# Project-PowerSwitch-Final.net
KiCad netlist of a schematic drawn in EAGLE
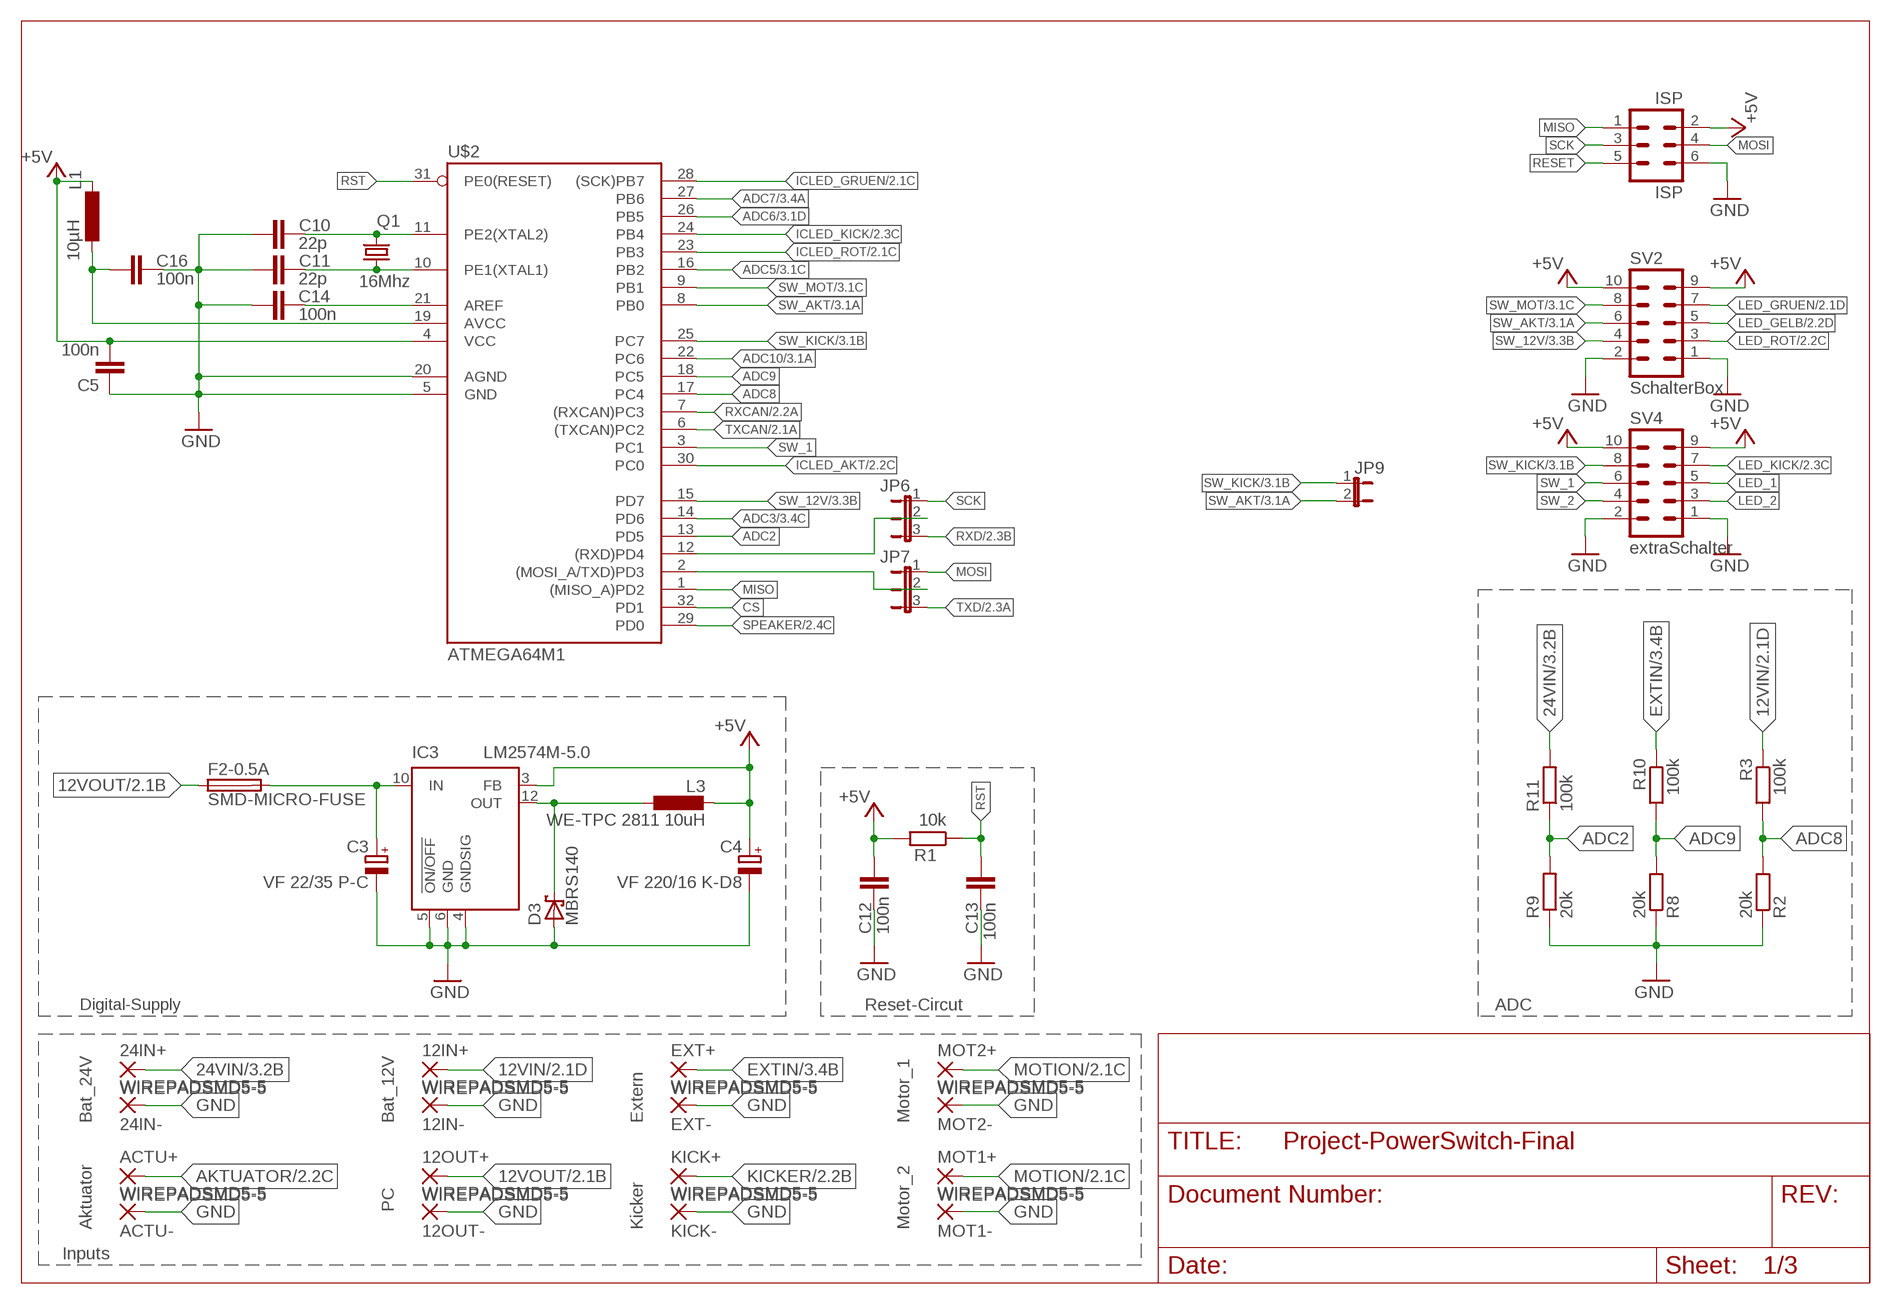
[diagram p0: schematic, sheet 1]
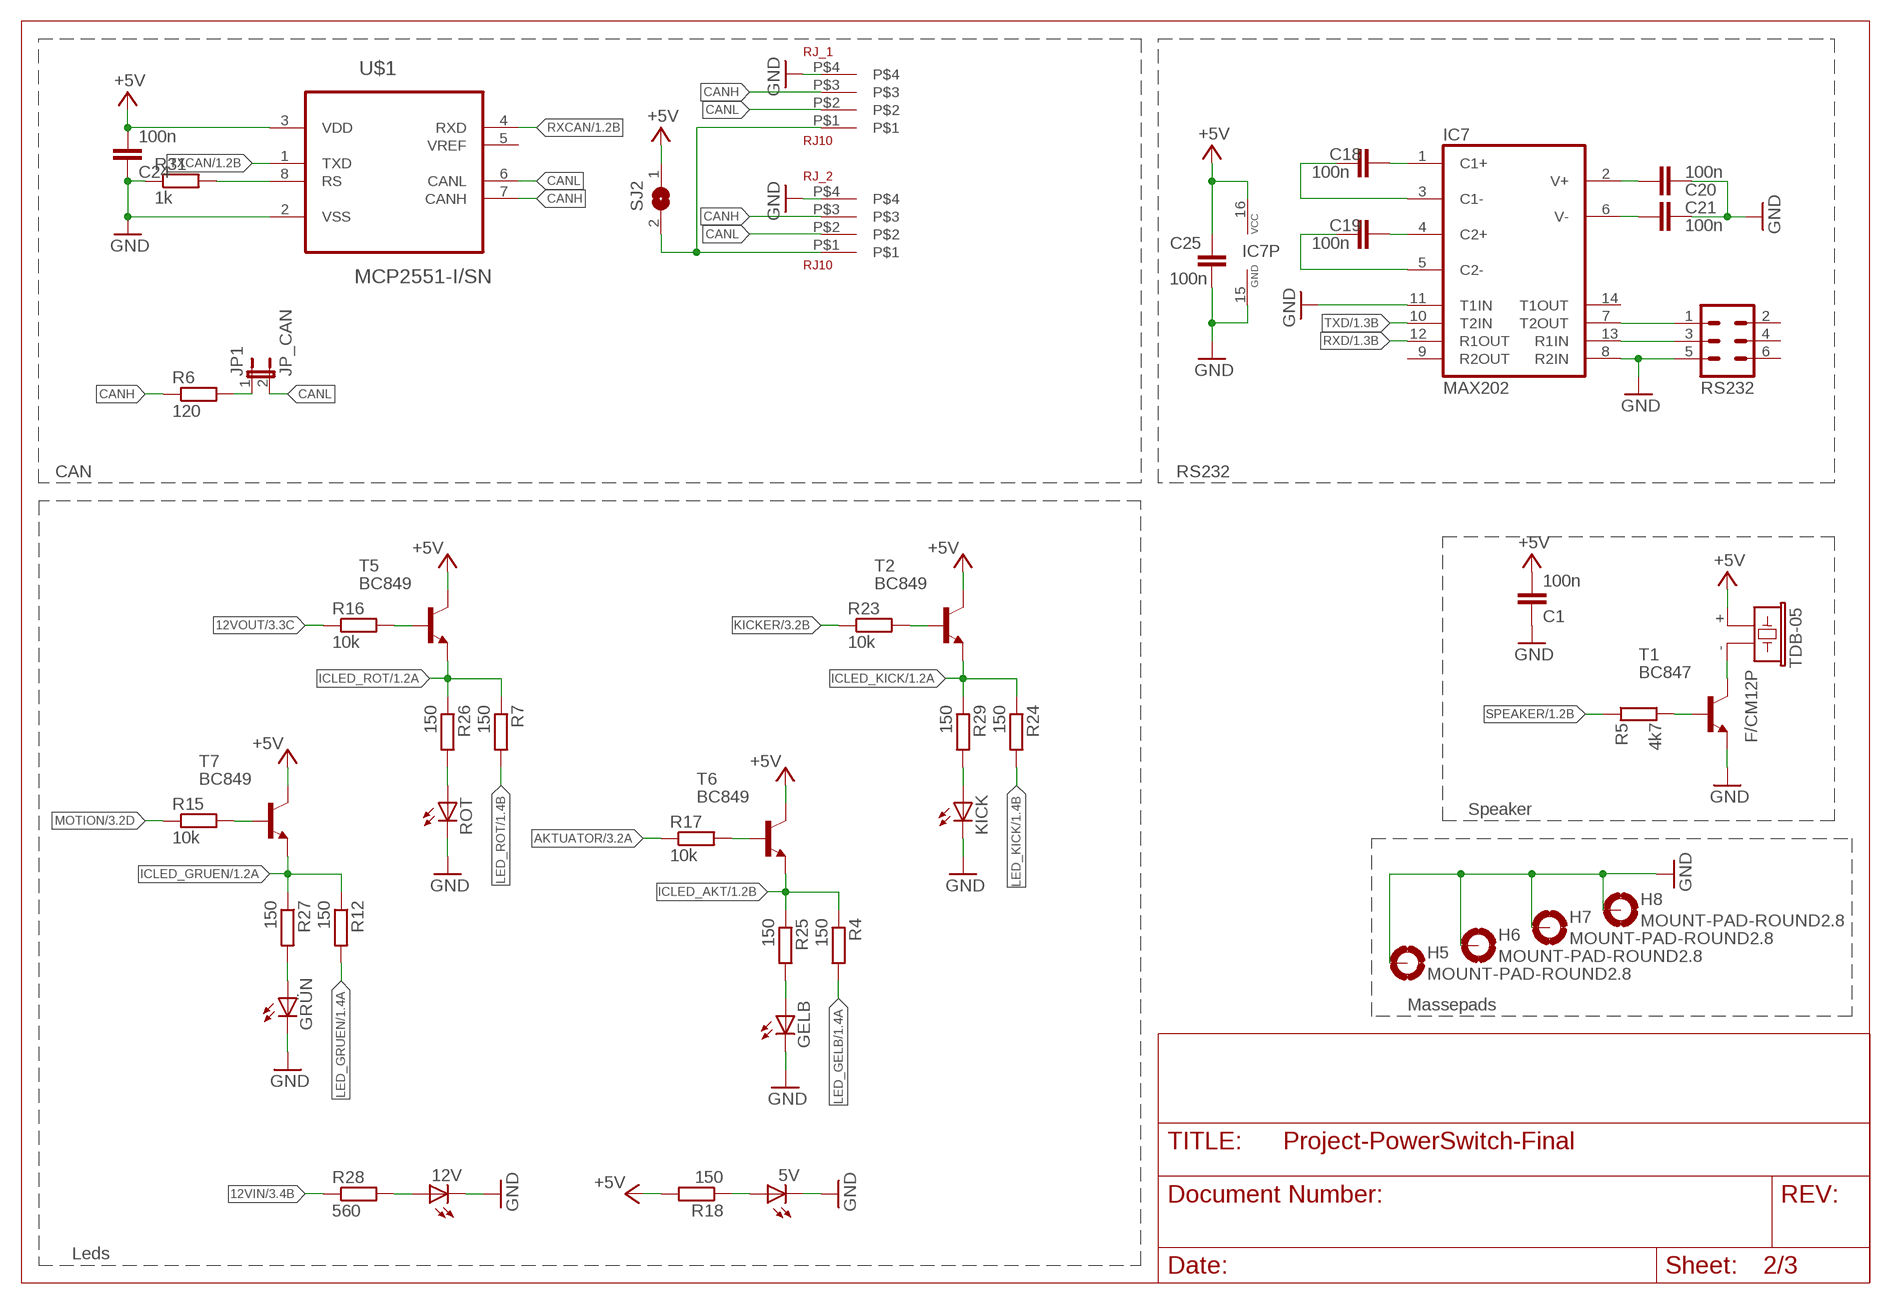
[diagram p1: schematic, sheet 2]
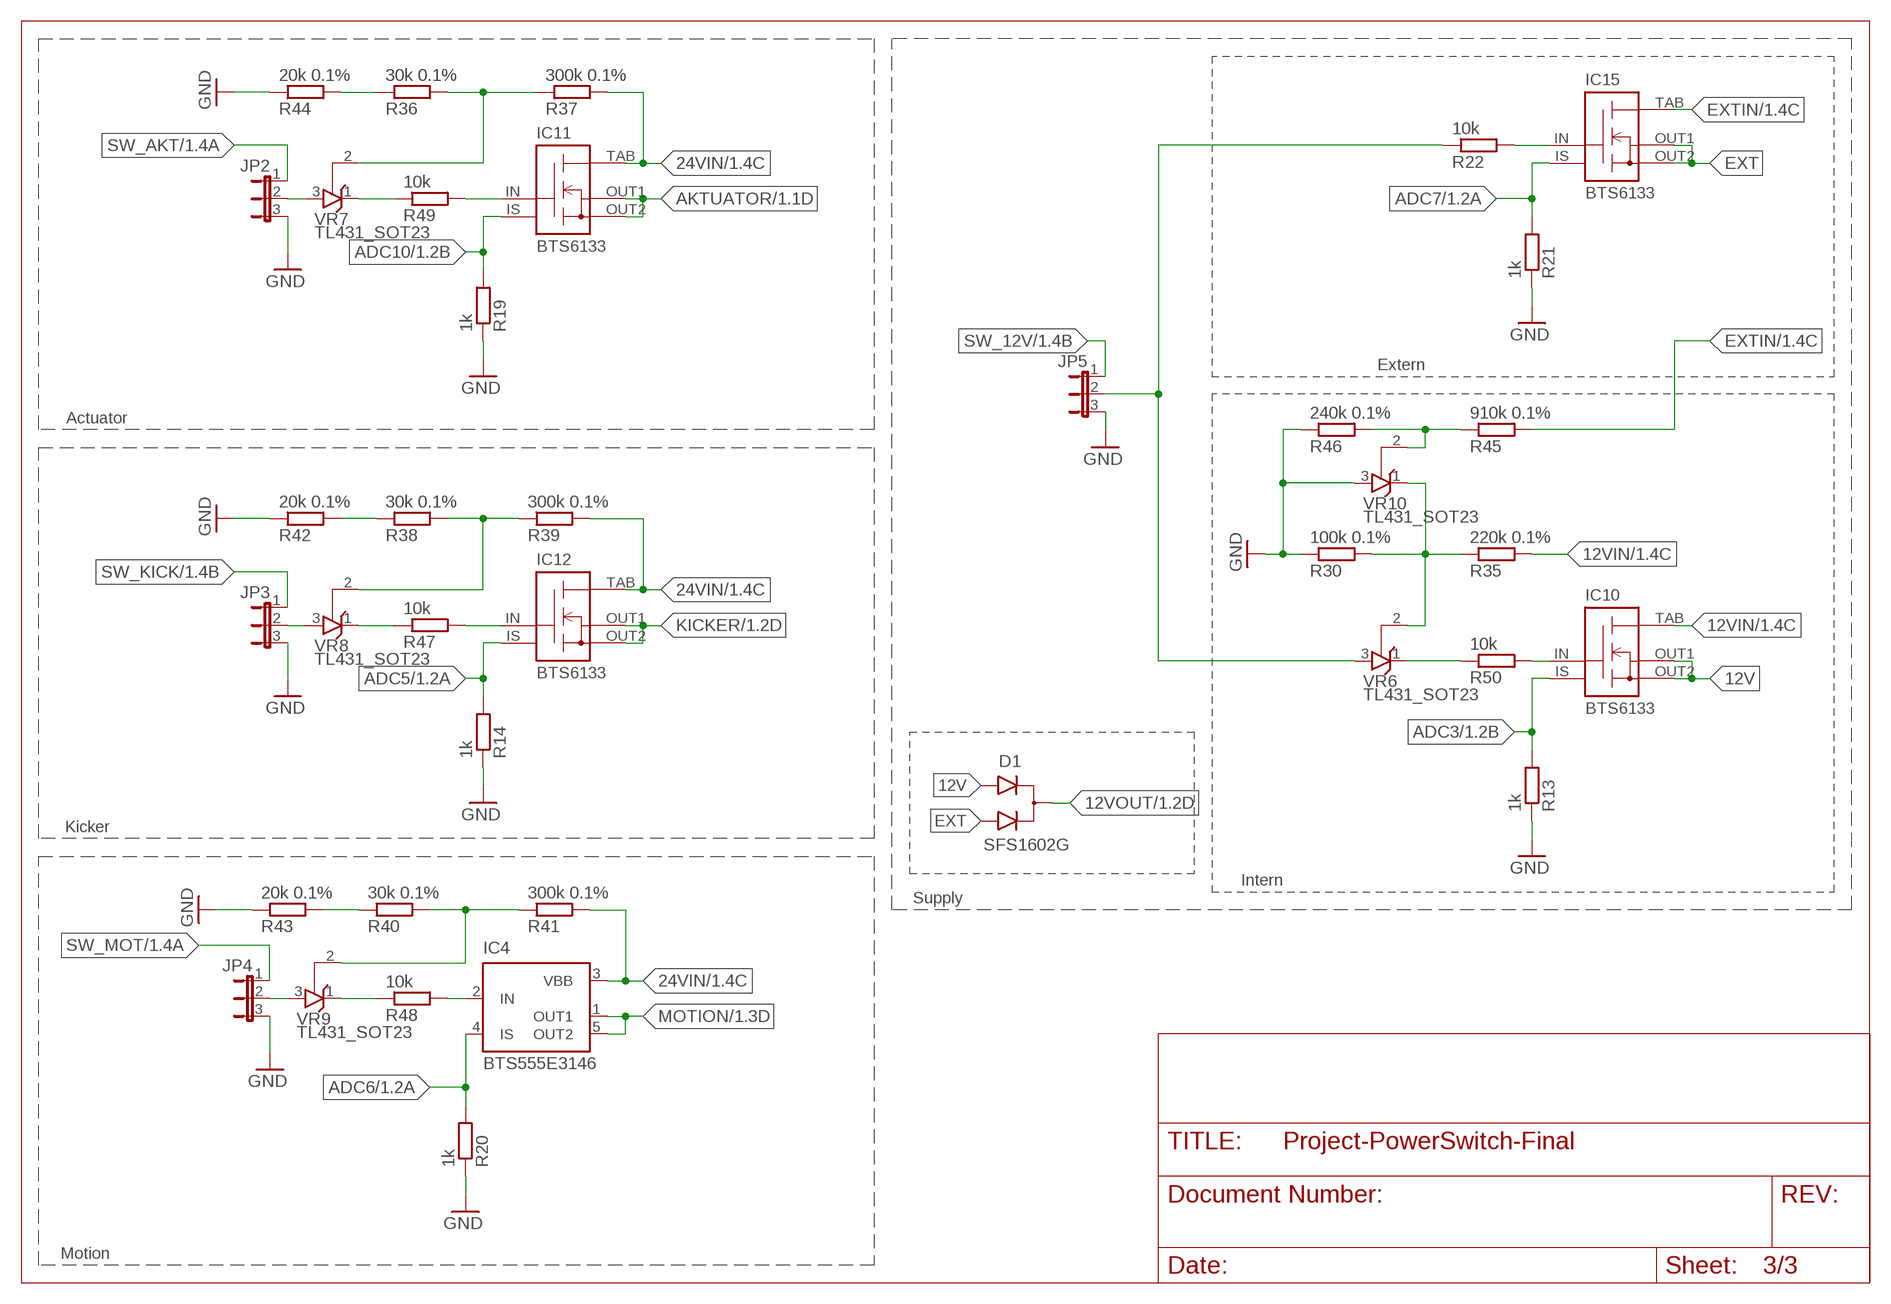
[diagram p2: schematic, sheet 3]

(export (version "E")
  (design (tool "Eeschema 10.0.6"))
  (components
    (comp (ref "D1")
      (value "SFS1602G")
      (footprint "eagle-import:D2PAK")
      (libsource (lib "eagle-import") (part "SFS160G"))
    )
    (comp (ref "IC4")
      (value "BTS555E3146")
      (footprint "eagle-import:TO220-52")
      (libsource (lib "eagle-import") (part "BTS555E3146"))
    )
    (comp (ref "IC10")
      (value "BTS6133")
      (footprint "eagle-import:TO252-51")
      (libsource (lib "eagle-import") (part "BTS6133"))
    )
    (comp (ref "IC11")
      (value "BTS6133")
      (footprint "eagle-import:TO252-51")
      (libsource (lib "eagle-import") (part "BTS6133"))
    )
    (comp (ref "IC12")
      (value "BTS6133")
      (footprint "eagle-import:TO252-51")
      (libsource (lib "eagle-import") (part "BTS6133"))
    )
    (comp (ref "IC15")
      (value "BTS6133")
      (footprint "eagle-import:TO252-51")
      (libsource (lib "eagle-import") (part "BTS6133"))
    )
    (comp (ref "JP2")
      (value "JP2E")
      (footprint "eagle-import:JP2")
      (libsource (lib "eagle-import") (part "JP2E"))
    )
    (comp (ref "JP3")
      (value "JP2E")
      (footprint "eagle-import:JP2")
      (libsource (lib "eagle-import") (part "JP2E"))
    )
    (comp (ref "JP4")
      (value "JP2E")
      (footprint "eagle-import:JP2")
      (libsource (lib "eagle-import") (part "JP2E"))
    )
    (comp (ref "JP5")
      (value "JP2E")
      (footprint "eagle-import:JP2")
      (libsource (lib "eagle-import") (part "JP2E"))
    )
    (comp (ref "R13")
      (value "1k")
      (footprint "eagle-import:R0805")
      (libsource (lib "eagle-import") (part "R-EU_R0805"))
    )
    (comp (ref "R14")
      (value "1k")
      (footprint "eagle-import:R0805")
      (libsource (lib "eagle-import") (part "R-EU_R0805"))
    )
    (comp (ref "R19")
      (value "1k")
      (footprint "eagle-import:R0805")
      (libsource (lib "eagle-import") (part "R-EU_R0805"))
    )
    (comp (ref "R20")
      (value "1k")
      (footprint "eagle-import:R0805")
      (libsource (lib "eagle-import") (part "R-EU_R0805"))
    )
    (comp (ref "R21")
      (value "1k")
      (footprint "eagle-import:R0805")
      (libsource (lib "eagle-import") (part "R-EU_R0805"))
    )
    (comp (ref "R22")
      (value "10k")
      (footprint "eagle-import:R0805")
      (libsource (lib "eagle-import") (part "R-EU_R0805"))
    )
    (comp (ref "R30")
      (value "100k 0.1%")
      (footprint "eagle-import:R0805")
      (libsource (lib "eagle-import") (part "R-EU_R0805"))
    )
    (comp (ref "R35")
      (value "220k 0.1%")
      (footprint "eagle-import:R0805")
      (libsource (lib "eagle-import") (part "R-EU_R0805"))
    )
    (comp (ref "R36")
      (value "30k 0.1%")
      (footprint "eagle-import:R0805")
      (libsource (lib "eagle-import") (part "R-EU_R0805"))
    )
    (comp (ref "R37")
      (value "300k 0.1%")
      (footprint "eagle-import:R0805")
      (libsource (lib "eagle-import") (part "R-EU_R0805"))
    )
    (comp (ref "R38")
      (value "30k 0.1%")
      (footprint "eagle-import:R0805")
      (libsource (lib "eagle-import") (part "R-EU_R0805"))
    )
    (comp (ref "R39")
      (value "300k 0.1%")
      (footprint "eagle-import:R0805")
      (libsource (lib "eagle-import") (part "R-EU_R0805"))
    )
    (comp (ref "R40")
      (value "30k 0.1%")
      (footprint "eagle-import:R0805")
      (libsource (lib "eagle-import") (part "R-EU_R0805"))
    )
    (comp (ref "R41")
      (value "300k 0.1%")
      (footprint "eagle-import:R0805")
      (libsource (lib "eagle-import") (part "R-EU_R0805"))
    )
    (comp (ref "R42")
      (value "20k 0.1%")
      (footprint "eagle-import:R0805")
      (libsource (lib "eagle-import") (part "R-EU_R0805"))
    )
    (comp (ref "R43")
      (value "20k 0.1%")
      (footprint "eagle-import:R0805")
      (libsource (lib "eagle-import") (part "R-EU_R0805"))
    )
    (comp (ref "R44")
      (value "20k 0.1%")
      (footprint "eagle-import:R0805")
      (libsource (lib "eagle-import") (part "R-EU_R0805"))
    )
    (comp (ref "R45")
      (value "910k 0.1%")
      (footprint "eagle-import:R0805")
      (libsource (lib "eagle-import") (part "R-EU_R0805"))
    )
    (comp (ref "R46")
      (value "240k 0.1%")
      (footprint "eagle-import:R0805")
      (libsource (lib "eagle-import") (part "R-EU_R0805"))
    )
    (comp (ref "R47")
      (value "10k")
      (footprint "eagle-import:R0805")
      (libsource (lib "eagle-import") (part "R-EU_R0805"))
    )
    (comp (ref "R48")
      (value "10k")
      (footprint "eagle-import:R0805")
      (libsource (lib "eagle-import") (part "R-EU_R0805"))
    )
    (comp (ref "R49")
      (value "10k")
      (footprint "eagle-import:R0805")
      (libsource (lib "eagle-import") (part "R-EU_R0805"))
    )
    (comp (ref "R50")
      (value "10k")
      (footprint "eagle-import:R0805")
      (libsource (lib "eagle-import") (part "R-EU_R0805"))
    )
    (comp (ref "VR6")
      (value "TL431_SOT23")
      (footprint "eagle-import:SOT23")
      (libsource (lib "eagle-import") (part "TL431_SOT23"))
    )
    (comp (ref "VR7")
      (value "TL431_SOT23")
      (footprint "eagle-import:SOT23")
      (libsource (lib "eagle-import") (part "TL431_SOT23"))
    )
    (comp (ref "VR8")
      (value "TL431_SOT23")
      (footprint "eagle-import:SOT23")
      (libsource (lib "eagle-import") (part "TL431_SOT23"))
    )
    (comp (ref "VR9")
      (value "TL431_SOT23")
      (footprint "eagle-import:SOT23")
      (libsource (lib "eagle-import") (part "TL431_SOT23"))
    )
    (comp (ref "VR10")
      (value "TL431_SOT23")
      (footprint "eagle-import:SOT23")
      (libsource (lib "eagle-import") (part "TL431_SOT23"))
    )
    (comp (ref "5V")
      (value "LEDCHIPLED_0805")
      (footprint "eagle-import:CHIPLED_0805")
      (libsource (lib "eagle-import") (part "LEDCHIPLED_0805"))
    )
    (comp (ref "12V")
      (value "LEDCHIPLED_0805")
      (footprint "eagle-import:CHIPLED_0805")
      (libsource (lib "eagle-import") (part "LEDCHIPLED_0805"))
    )
    (comp (ref "C1")
      (value "100n")
      (footprint "eagle-import:C0603")
      (libsource (lib "eagle-import") (part "C-EUC0603"))
    )
    (comp (ref "C18")
      (value "100n")
      (footprint "eagle-import:C0603K")
      (libsource (lib "eagle-import") (part "C-EUC0603K"))
    )
    (comp (ref "C19")
      (value "100n")
      (footprint "eagle-import:C0603K")
      (libsource (lib "eagle-import") (part "C-EUC0603K"))
    )
    (comp (ref "C20")
      (value "100n")
      (footprint "eagle-import:C0603K")
      (libsource (lib "eagle-import") (part "C-EUC0603K"))
    )
    (comp (ref "C21")
      (value "100n")
      (footprint "eagle-import:C0603K")
      (libsource (lib "eagle-import") (part "C-EUC0603K"))
    )
    (comp (ref "C24")
      (value "100n")
      (footprint "eagle-import:C0603")
      (libsource (lib "eagle-import") (part "C-EUC0603"))
    )
    (comp (ref "C25")
      (value "100n")
      (footprint "eagle-import:C0603K")
      (libsource (lib "eagle-import") (part "C-EUC0603K"))
    )
    (comp (ref "GELB")
      (value "LEDCHIPLED_0805")
      (footprint "eagle-import:CHIPLED_0805")
      (libsource (lib "eagle-import") (part "LEDCHIPLED_0805"))
    )
    (comp (ref "GRÜN")
      (value "LEDCHIPLED_0805")
      (footprint "eagle-import:CHIPLED_0805")
      (libsource (lib "eagle-import") (part "LEDCHIPLED_0805"))
    )
    (comp (ref "H5")
      (value "MOUNT-PAD-ROUND2.8")
      (footprint "eagle-import:2,8-PAD")
      (libsource (lib "eagle-import") (part "MOUNT-PAD-ROUND2.8"))
    )
    (comp (ref "H6")
      (value "MOUNT-PAD-ROUND2.8")
      (footprint "eagle-import:2,8-PAD")
      (libsource (lib "eagle-import") (part "MOUNT-PAD-ROUND2.8"))
    )
    (comp (ref "H7")
      (value "MOUNT-PAD-ROUND2.8")
      (footprint "eagle-import:2,8-PAD")
      (libsource (lib "eagle-import") (part "MOUNT-PAD-ROUND2.8"))
    )
    (comp (ref "H8")
      (value "MOUNT-PAD-ROUND2.8")
      (footprint "eagle-import:2,8-PAD")
      (libsource (lib "eagle-import") (part "MOUNT-PAD-ROUND2.8"))
    )
    (comp (ref "IC7")
      (value "MAX202")
      (footprint "eagle-import:SO16")
      (fields (field (name "MPN") "MAX3232CSE"))
      (libsource (lib "eagle-import") (part "MAX3232SEC"))
    )
    (comp (ref "JP1")
      (value "JP_CAN")
      (footprint "eagle-import:JP1")
      (libsource (lib "eagle-import") (part "JP1E"))
    )
    (comp (ref "KICK")
      (value "LEDCHIPLED_0805")
      (footprint "eagle-import:CHIPLED_0805")
      (libsource (lib "eagle-import") (part "LEDCHIPLED_0805"))
    )
    (comp (ref "R4")
      (value "150")
      (footprint "eagle-import:R0805")
      (libsource (lib "eagle-import") (part "R-EU_R0805"))
    )
    (comp (ref "R5")
      (value "4k7")
      (footprint "eagle-import:R0805")
      (libsource (lib "eagle-import") (part "R-EU_R0805"))
    )
    (comp (ref "R6")
      (value "120")
      (footprint "eagle-import:M0805")
      (libsource (lib "eagle-import") (part "R-EU_M0805"))
    )
    (comp (ref "R7")
      (value "150")
      (footprint "eagle-import:R0805")
      (libsource (lib "eagle-import") (part "R-EU_R0805"))
    )
    (comp (ref "R12")
      (value "150")
      (footprint "eagle-import:R0805")
      (libsource (lib "eagle-import") (part "R-EU_R0805"))
    )
    (comp (ref "R15")
      (value "10k")
      (footprint "eagle-import:R0805")
      (libsource (lib "eagle-import") (part "R-EU_R0805"))
    )
    (comp (ref "R16")
      (value "10k")
      (footprint "eagle-import:R0805")
      (libsource (lib "eagle-import") (part "R-EU_R0805"))
    )
    (comp (ref "R17")
      (value "10k")
      (footprint "eagle-import:R0805")
      (libsource (lib "eagle-import") (part "R-EU_R0805"))
    )
    (comp (ref "R18")
      (value "150")
      (footprint "eagle-import:R0805")
      (libsource (lib "eagle-import") (part "R-EU_R0805"))
    )
    (comp (ref "R23")
      (value "10k")
      (footprint "eagle-import:R0805")
      (libsource (lib "eagle-import") (part "R-EU_R0805"))
    )
    (comp (ref "R24")
      (value "150")
      (footprint "eagle-import:R0805")
      (libsource (lib "eagle-import") (part "R-EU_R0805"))
    )
    (comp (ref "R25")
      (value "150")
      (footprint "eagle-import:R0805")
      (libsource (lib "eagle-import") (part "R-EU_R0805"))
    )
    (comp (ref "R26")
      (value "150")
      (footprint "eagle-import:R0805")
      (libsource (lib "eagle-import") (part "R-EU_R0805"))
    )
    (comp (ref "R27")
      (value "150")
      (footprint "eagle-import:R0805")
      (libsource (lib "eagle-import") (part "R-EU_R0805"))
    )
    (comp (ref "R28")
      (value "560")
      (footprint "eagle-import:R0805")
      (libsource (lib "eagle-import") (part "R-EU_R0805"))
    )
    (comp (ref "R29")
      (value "150")
      (footprint "eagle-import:R0805")
      (libsource (lib "eagle-import") (part "R-EU_R0805"))
    )
    (comp (ref "R31")
      (value "1k")
      (footprint "eagle-import:R0805")
      (libsource (lib "eagle-import") (part "R-EU_R0805"))
    )
    (comp (ref "RJ_1")
      (value "RJ10")
      (footprint "eagle-import:RJ10")
      (libsource (lib "eagle-import") (part "RJ10"))
    )
    (comp (ref "RJ_2")
      (value "RJ10")
      (footprint "eagle-import:RJ10")
      (libsource (lib "eagle-import") (part "RJ10"))
    )
    (comp (ref "ROT")
      (value "LEDCHIPLED_0805")
      (footprint "eagle-import:CHIPLED_0805")
      (libsource (lib "eagle-import") (part "LEDCHIPLED_0805"))
    )
    (comp (ref "RS232")
      (value "ML6")
      (footprint "eagle-import:ML6")
      (libsource (lib "eagle-import") (part "ML6"))
    )
    (comp (ref "SJ2") (value "SJ") (footprint "eagle-import:SJ") (libsource (lib "eagle-import") (part "SJ")))
    (comp (ref "T1")
      (value "BC847")
      (footprint "eagle-import:SOT23")
      (libsource (lib "eagle-import") (part "BC847"))
    )
    (comp (ref "T2")
      (value "BC849")
      (footprint "eagle-import:SOT23")
      (libsource (lib "eagle-import") (part "BC849"))
    )
    (comp (ref "T5")
      (value "BC849")
      (footprint "eagle-import:SOT23")
      (libsource (lib "eagle-import") (part "BC849"))
    )
    (comp (ref "T6")
      (value "BC849")
      (footprint "eagle-import:SOT23")
      (libsource (lib "eagle-import") (part "BC849"))
    )
    (comp (ref "T7")
      (value "BC849")
      (footprint "eagle-import:SOT23")
      (libsource (lib "eagle-import") (part "BC849"))
    )
    (comp (ref "TDB-05")
      (value "F/CM12P")
      (footprint "eagle-import:F_CM12P")
      (libsource (lib "eagle-import") (part "F/CM12P"))
    )
    (comp (ref "U$1")
      (value "MCP2551-I/SN")
      (footprint "eagle-import:SOIC127P600X175-8N")
      (libsource (lib "eagle-import") (part "MCP2551-I/SN"))
    )
    (comp (ref "12IN+")
      (value "WIREPADSMD5-5")
      (footprint "eagle-import:5-5")
      (libsource (lib "eagle-import") (part "WIREPADSMD5-5"))
    )
    (comp (ref "12IN-")
      (value "WIREPADSMD5-5")
      (footprint "eagle-import:5-5")
      (libsource (lib "eagle-import") (part "WIREPADSMD5-5"))
    )
    (comp (ref "12OUT+")
      (value "WIREPADSMD5-5")
      (footprint "eagle-import:5-5")
      (libsource (lib "eagle-import") (part "WIREPADSMD5-5"))
    )
    (comp (ref "12OUT-")
      (value "WIREPADSMD5-5")
      (footprint "eagle-import:5-5")
      (libsource (lib "eagle-import") (part "WIREPADSMD5-5"))
    )
    (comp (ref "24IN+")
      (value "WIREPADSMD5-5")
      (footprint "eagle-import:5-5")
      (libsource (lib "eagle-import") (part "WIREPADSMD5-5"))
    )
    (comp (ref "24IN-")
      (value "WIREPADSMD5-5")
      (footprint "eagle-import:5-5")
      (libsource (lib "eagle-import") (part "WIREPADSMD5-5"))
    )
    (comp (ref "ACTU+")
      (value "WIREPADSMD5-5")
      (footprint "eagle-import:5-5")
      (libsource (lib "eagle-import") (part "WIREPADSMD5-5"))
    )
    (comp (ref "ACTU-")
      (value "WIREPADSMD5-5")
      (footprint "eagle-import:5-5")
      (libsource (lib "eagle-import") (part "WIREPADSMD5-5"))
    )
    (comp (ref "C3")
      (value "VF 22/35 P-C")
      (footprint "eagle-import:PANASONIC_C")
      (libsource (lib "eagle-import") (part "CPOL-EUC"))
    )
    (comp (ref "C4")
      (value "VF 220/16 K-D8")
      (footprint "eagle-import:PANASONIC_D")
      (libsource (lib "eagle-import") (part "CPOL-EUD"))
    )
    (comp (ref "C5")
      (value "100n")
      (footprint "eagle-import:C0603K")
      (libsource (lib "eagle-import") (part "C-EUC0603K"))
    )
    (comp (ref "C10")
      (value "22p")
      (footprint "eagle-import:C0603K")
      (libsource (lib "eagle-import") (part "C-EUC0603K"))
    )
    (comp (ref "C11")
      (value "22p")
      (footprint "eagle-import:C0603K")
      (libsource (lib "eagle-import") (part "C-EUC0603K"))
    )
    (comp (ref "C12")
      (value "100n")
      (footprint "eagle-import:C0603K")
      (libsource (lib "eagle-import") (part "C-EUC0603K"))
    )
    (comp (ref "C13")
      (value "100n")
      (footprint "eagle-import:C0603K")
      (libsource (lib "eagle-import") (part "C-EUC0603K"))
    )
    (comp (ref "C14")
      (value "100n")
      (footprint "eagle-import:C0603K")
      (libsource (lib "eagle-import") (part "C-EUC0603K"))
    )
    (comp (ref "C16")
      (value "100n")
      (footprint "eagle-import:C0603K")
      (libsource (lib "eagle-import") (part "C-EUC0603K"))
    )
    (comp (ref "D3")
      (value "MBRS140")
      (footprint "eagle-import:SMB")
      (libsource (lib "eagle-import") (part "SCHOTTKY-DIODESMD"))
    )
    (comp (ref "EXT+")
      (value "WIREPADSMD5-5")
      (footprint "eagle-import:5-5")
      (libsource (lib "eagle-import") (part "WIREPADSMD5-5"))
    )
    (comp (ref "EXT-")
      (value "WIREPADSMD5-5")
      (footprint "eagle-import:5-5")
      (libsource (lib "eagle-import") (part "WIREPADSMD5-5"))
    )
    (comp (ref "F2-0.5A")
      (value "SMD-MICRO-FUSE")
      (footprint "eagle-import:SMD-6,1X2,6")
      (libsource (lib "eagle-import") (part "SMD-MICRO-FUSE"))
    )
    (comp (ref "IC3")
      (value "LM2574M-5.0")
      (footprint "eagle-import:SO14W")
      (libsource (lib "eagle-import") (part "LM2574?-M5.0"))
    )
    (comp (ref "ISP")
      (value "ISP")
      (footprint "eagle-import:ML6")
      (libsource (lib "eagle-import") (part "ML6"))
    )
    (comp (ref "JP6")
      (value "JP2E")
      (footprint "eagle-import:JP2")
      (libsource (lib "eagle-import") (part "JP2E"))
    )
    (comp (ref "JP7")
      (value "JP2E")
      (footprint "eagle-import:JP2")
      (libsource (lib "eagle-import") (part "JP2E"))
    )
    (comp (ref "JP9")
      (value "JP1E")
      (footprint "eagle-import:JP1")
      (libsource (lib "eagle-import") (part "JP1E"))
    )
    (comp (ref "KICK+")
      (value "WIREPADSMD5-5")
      (footprint "eagle-import:5-5")
      (libsource (lib "eagle-import") (part "WIREPADSMD5-5"))
    )
    (comp (ref "KICK-")
      (value "WIREPADSMD5-5")
      (footprint "eagle-import:5-5")
      (libsource (lib "eagle-import") (part "WIREPADSMD5-5"))
    )
    (comp (ref "L1")
      (value "10µH")
      (footprint "eagle-import:R0805")
      (libsource (lib "eagle-import") (part "L-EU-0805L0805"))
    )
    (comp (ref "L3")
      (value "WE-TPC 2811 10uH")
      (footprint "eagle-import:POWER-CHOKE_WE-TPC")
      (libsource (lib "eagle-import") (part "L-EUWE-TPC"))
    )
    (comp (ref "MOT1+")
      (value "WIREPADSMD5-5")
      (footprint "eagle-import:5-5")
      (libsource (lib "eagle-import") (part "WIREPADSMD5-5"))
    )
    (comp (ref "MOT1-")
      (value "WIREPADSMD5-5")
      (footprint "eagle-import:5-5")
      (libsource (lib "eagle-import") (part "WIREPADSMD5-5"))
    )
    (comp (ref "MOT2+")
      (value "WIREPADSMD5-5")
      (footprint "eagle-import:5-5")
      (libsource (lib "eagle-import") (part "WIREPADSMD5-5"))
    )
    (comp (ref "MOT2-")
      (value "WIREPADSMD5-5")
      (footprint "eagle-import:5-5")
      (libsource (lib "eagle-import") (part "WIREPADSMD5-5"))
    )
    (comp (ref "Q1")
      (value "16Mhz")
      (footprint "eagle-import:HC49U-V@1")
      (libsource (lib "eagle-import") (part "CRYTALHC49U-V"))
    )
    (comp (ref "R1")
      (value "10k")
      (footprint "eagle-import:R0805")
      (libsource (lib "eagle-import") (part "R-EU_R0805"))
    )
    (comp (ref "R2")
      (value "20k")
      (footprint "eagle-import:R0805")
      (libsource (lib "eagle-import") (part "R-EU_R0805"))
    )
    (comp (ref "R3")
      (value "100k")
      (footprint "eagle-import:R0805")
      (libsource (lib "eagle-import") (part "R-EU_R0805"))
    )
    (comp (ref "R8")
      (value "20k")
      (footprint "eagle-import:R0805")
      (libsource (lib "eagle-import") (part "R-EU_R0805"))
    )
    (comp (ref "R9")
      (value "20k")
      (footprint "eagle-import:R0805")
      (libsource (lib "eagle-import") (part "R-EU_R0805"))
    )
    (comp (ref "R10")
      (value "100k")
      (footprint "eagle-import:R0805")
      (libsource (lib "eagle-import") (part "R-EU_R0805"))
    )
    (comp (ref "R11")
      (value "100k")
      (footprint "eagle-import:R0805")
      (libsource (lib "eagle-import") (part "R-EU_R0805"))
    )
    (comp (ref "SV2")
      (value "SchalterBox")
      (footprint "eagle-import:ML10")
      (libsource (lib "eagle-import") (part "ML10"))
    )
    (comp (ref "SV4")
      (value "extraSchalter")
      (footprint "eagle-import:ML10")
      (libsource (lib "eagle-import") (part "ML10"))
    )
    (comp (ref "U$2")
      (value "ATMEGA64M1")
      (footprint "eagle-import:TQFP32-08")
      (libsource (lib "eagle-import") (part "ATMEGA64M1"))
    )
  )
  (nets
    (net (code "1") (name "+5V") (class "Default")
      (node (ref "C1") (pin "2") (pinfunction "2_2") (pintype "passive"))
      (node (ref "C12") (pin "2") (pinfunction "2_2") (pintype "passive"))
      (node (ref "C24") (pin "2") (pinfunction "2_2") (pintype "passive"))
      (node (ref "C25") (pin "1") (pinfunction "1_1") (pintype "passive"))
      (node (ref "C4") (pin "+") (pinfunction "+_+") (pintype "passive"))
      (node (ref "C5") (pin "2") (pinfunction "2_2") (pintype "passive"))
      (node (ref "IC3") (pin "3") (pinfunction "FB_3") (pintype "input"))
      (node (ref "IC7") (pin "16") (pinfunction "VCC_16") (pintype "power_in"))
      (node (ref "ISP") (pin "2") (pinfunction "2_2") (pintype "passive"))
      (node (ref "L1") (pin "2") (pinfunction "2_2") (pintype "passive"))
      (node (ref "L3") (pin "2") (pinfunction "2_2") (pintype "passive"))
      (node (ref "R1") (pin "2") (pinfunction "2_2") (pintype "passive"))
      (node (ref "R18") (pin "2") (pinfunction "2_2") (pintype "passive"))
      (node (ref "SJ2") (pin "1") (pinfunction "1_1") (pintype "passive"))
      (node (ref "SV2") (pin "10") (pinfunction "10_10") (pintype "passive"))
      (node (ref "SV2") (pin "9") (pinfunction "9_9") (pintype "passive"))
      (node (ref "SV4") (pin "10") (pinfunction "10_10") (pintype "passive"))
      (node (ref "SV4") (pin "9") (pinfunction "9_9") (pintype "passive"))
      (node (ref "T2") (pin "3") (pinfunction "C_3") (pintype "passive"))
      (node (ref "T5") (pin "3") (pinfunction "C_3") (pintype "passive"))
      (node (ref "T6") (pin "3") (pinfunction "C_3") (pintype "passive"))
      (node (ref "T7") (pin "3") (pinfunction "C_3") (pintype "passive"))
      (node (ref "TDB-05") (pin "+") (pinfunction "1_+") (pintype "passive"))
      (node (ref "U$1") (pin "3") (pinfunction "VDD_3") (pintype "power_in"))
      (node (ref "U$2") (pin "4") (pinfunction "VCC_4") (pintype "bidirectional"))
    )
    (net (code "2") (name "12V") (class "Default")
      (node (ref "D1") (pin "P$1") (pinfunction "P$1_P$1") (pintype "bidirectional"))
      (node (ref "IC10") (pin "OUT1") (pinfunction "OUT_OUT1") (pintype "passive"))
      (node (ref "IC10") (pin "OUT2") (pinfunction "OUT_OUT2") (pintype "passive"))
    )
    (net (code "3") (name "12VIN") (class "Default")
      (node (ref "12IN+") (pin "P$1") (pinfunction "P_P$1") (pintype "passive"))
      (node (ref "IC10") (pin "TAB") (pinfunction "VBB_TAB") (pintype "power_in"))
      (node (ref "R28") (pin "1") (pinfunction "1_1") (pintype "passive"))
      (node (ref "R3") (pin "1") (pinfunction "1_1") (pintype "passive"))
      (node (ref "R35") (pin "2") (pinfunction "2_2") (pintype "passive"))
    )
    (net (code "4") (name "12VOUT") (class "Default")
      (node (ref "12OUT+") (pin "P$1") (pinfunction "P_P$1") (pintype "passive"))
      (node (ref "D1") (pin "P$3") (pinfunction "P$3_P$3") (pintype "bidirectional"))
      (node (ref "F2-0.5A") (pin "1") (pinfunction "1_1") (pintype "passive"))
      (node (ref "R16") (pin "1") (pinfunction "1_1") (pintype "passive"))
    )
    (net (code "5") (name "24VIN") (class "Default")
      (node (ref "24IN+") (pin "P$1") (pinfunction "P_P$1") (pintype "passive"))
      (node (ref "IC11") (pin "TAB") (pinfunction "VBB_TAB") (pintype "power_in"))
      (node (ref "IC12") (pin "TAB") (pinfunction "VBB_TAB") (pintype "power_in"))
      (node (ref "IC4") (pin "3") (pinfunction "VBB_3") (pintype "passive"))
      (node (ref "R11") (pin "2") (pinfunction "2_2") (pintype "passive"))
      (node (ref "R37") (pin "2") (pinfunction "2_2") (pintype "passive"))
      (node (ref "R39") (pin "2") (pinfunction "2_2") (pintype "passive"))
      (node (ref "R41") (pin "2") (pinfunction "2_2") (pintype "passive"))
    )
    (net (code "6") (name "ADC2") (class "Default")
      (node (ref "R11") (pin "1") (pinfunction "1_1") (pintype "passive"))
      (node (ref "R9") (pin "2") (pinfunction "2_2") (pintype "passive"))
      (node (ref "U$2") (pin "13") (pinfunction "PD5_13") (pintype "bidirectional"))
    )
    (net (code "7") (name "ADC3") (class "Default")
      (node (ref "IC10") (pin "IS") (pinfunction "IS_IS") (pintype "passive"))
      (node (ref "R13") (pin "2") (pinfunction "2_2") (pintype "passive"))
      (node (ref "U$2") (pin "14") (pinfunction "PD6_14") (pintype "bidirectional"))
    )
    (net (code "8") (name "ADC5") (class "Default")
      (node (ref "IC12") (pin "IS") (pinfunction "IS_IS") (pintype "passive"))
      (node (ref "R14") (pin "2") (pinfunction "2_2") (pintype "passive"))
      (node (ref "U$2") (pin "16") (pinfunction "PB2_16") (pintype "bidirectional"))
    )
    (net (code "9") (name "ADC6") (class "Default")
      (node (ref "IC4") (pin "4") (pinfunction "IS_4") (pintype "passive"))
      (node (ref "R20") (pin "2") (pinfunction "2_2") (pintype "passive"))
      (node (ref "U$2") (pin "26") (pinfunction "PB5_26") (pintype "bidirectional"))
    )
    (net (code "10") (name "ADC7") (class "Default")
      (node (ref "IC15") (pin "IS") (pinfunction "IS_IS") (pintype "passive"))
      (node (ref "R21") (pin "2") (pinfunction "2_2") (pintype "passive"))
      (node (ref "U$2") (pin "27") (pinfunction "PB6_27") (pintype "bidirectional"))
    )
    (net (code "11") (name "ADC8") (class "Default")
      (node (ref "R2") (pin "2") (pinfunction "2_2") (pintype "passive"))
      (node (ref "R3") (pin "2") (pinfunction "2_2") (pintype "passive"))
      (node (ref "U$2") (pin "17") (pinfunction "PC4_17") (pintype "bidirectional"))
    )
    (net (code "12") (name "ADC9") (class "Default")
      (node (ref "R10") (pin "2") (pinfunction "2_2") (pintype "passive"))
      (node (ref "R8") (pin "2") (pinfunction "2_2") (pintype "passive"))
      (node (ref "U$2") (pin "18") (pinfunction "PC5_18") (pintype "bidirectional"))
    )
    (net (code "13") (name "ADC10") (class "Default")
      (node (ref "IC11") (pin "IS") (pinfunction "IS_IS") (pintype "passive"))
      (node (ref "R19") (pin "2") (pinfunction "2_2") (pintype "passive"))
      (node (ref "U$2") (pin "22") (pinfunction "PC6_22") (pintype "bidirectional"))
    )
    (net (code "14") (name "AKTUATOR") (class "Default")
      (node (ref "ACTU+") (pin "P$1") (pinfunction "P_P$1") (pintype "passive"))
      (node (ref "IC11") (pin "OUT1") (pinfunction "OUT_OUT1") (pintype "passive"))
      (node (ref "IC11") (pin "OUT2") (pinfunction "OUT_OUT2") (pintype "passive"))
      (node (ref "R17") (pin "1") (pinfunction "1_1") (pintype "passive"))
    )
    (net (code "15") (name "CANH") (class "Default")
      (node (ref "R6") (pin "1") (pinfunction "1_1") (pintype "passive"))
      (node (ref "RJ_1") (pin "P$3") (pinfunction "P$3_P$3") (pintype "bidirectional"))
      (node (ref "RJ_2") (pin "P$3") (pinfunction "P$3_P$3") (pintype "bidirectional"))
      (node (ref "U$1") (pin "7") (pinfunction "CANH_7") (pintype "bidirectional"))
    )
    (net (code "16") (name "CANL") (class "Default")
      (node (ref "JP1") (pin "2") (pinfunction "2_2") (pintype "passive"))
      (node (ref "RJ_1") (pin "P$2") (pinfunction "P$2_P$2") (pintype "bidirectional"))
      (node (ref "RJ_2") (pin "P$2") (pinfunction "P$2_P$2") (pintype "bidirectional"))
      (node (ref "U$1") (pin "6") (pinfunction "CANL_6") (pintype "bidirectional"))
    )
    (net (code "17") (name "CS") (class "Default")
      (node (ref "U$2") (pin "32") (pinfunction "PD1_32") (pintype "bidirectional"))
    )
    (net (code "18") (name "EXT") (class "Default")
      (node (ref "D1") (pin "P$2") (pinfunction "P$2_P$2") (pintype "bidirectional"))
      (node (ref "IC15") (pin "OUT1") (pinfunction "OUT_OUT1") (pintype "passive"))
      (node (ref "IC15") (pin "OUT2") (pinfunction "OUT_OUT2") (pintype "passive"))
    )
    (net (code "19") (name "EXTIN") (class "Default")
      (node (ref "EXT+") (pin "P$1") (pinfunction "P_P$1") (pintype "passive"))
      (node (ref "IC15") (pin "TAB") (pinfunction "VBB_TAB") (pintype "power_in"))
      (node (ref "R10") (pin "1") (pinfunction "1_1") (pintype "passive"))
      (node (ref "R45") (pin "2") (pinfunction "2_2") (pintype "passive"))
    )
    (net (code "20") (name "GND") (class "Default")
      (node (ref "12IN-") (pin "P$1") (pinfunction "P_P$1") (pintype "passive"))
      (node (ref "12OUT-") (pin "P$1") (pinfunction "P_P$1") (pintype "passive"))
      (node (ref "12V") (pin "C") (pinfunction "C_C") (pintype "passive"))
      (node (ref "24IN-") (pin "P$1") (pinfunction "P_P$1") (pintype "passive"))
      (node (ref "5V") (pin "C") (pinfunction "C_C") (pintype "passive"))
      (node (ref "ACTU-") (pin "P$1") (pinfunction "P_P$1") (pintype "passive"))
      (node (ref "C1") (pin "1") (pinfunction "1_1") (pintype "passive"))
      (node (ref "C10") (pin "1") (pinfunction "1_1") (pintype "passive"))
      (node (ref "C11") (pin "1") (pinfunction "1_1") (pintype "passive"))
      (node (ref "C12") (pin "1") (pinfunction "1_1") (pintype "passive"))
      (node (ref "C13") (pin "1") (pinfunction "1_1") (pintype "passive"))
      (node (ref "C14") (pin "1") (pinfunction "1_1") (pintype "passive"))
      (node (ref "C16") (pin "2") (pinfunction "2_2") (pintype "passive"))
      (node (ref "C20") (pin "2") (pinfunction "2_2") (pintype "passive"))
      (node (ref "C21") (pin "2") (pinfunction "2_2") (pintype "passive"))
      (node (ref "C24") (pin "1") (pinfunction "1_1") (pintype "passive"))
      (node (ref "C25") (pin "2") (pinfunction "2_2") (pintype "passive"))
      (node (ref "C3") (pin "-") (pinfunction "-_-") (pintype "passive"))
      (node (ref "C4") (pin "-") (pinfunction "-_-") (pintype "passive"))
      (node (ref "C5") (pin "1") (pinfunction "1_1") (pintype "passive"))
      (node (ref "D3") (pin "A") (pinfunction "A_A") (pintype "passive"))
      (node (ref "EXT-") (pin "P$1") (pinfunction "P_P$1") (pintype "passive"))
      (node (ref "GELB") (pin "C") (pinfunction "C_C") (pintype "passive"))
      (node (ref "GRÜN") (pin "C") (pinfunction "C_C") (pintype "passive"))
      (node (ref "H5") (pin "B2,8") (pinfunction "MOUNT_B2,8") (pintype "passive"))
      (node (ref "H6") (pin "B2,8") (pinfunction "MOUNT_B2,8") (pintype "passive"))
      (node (ref "H7") (pin "B2,8") (pinfunction "MOUNT_B2,8") (pintype "passive"))
      (node (ref "H8") (pin "B2,8") (pinfunction "MOUNT_B2,8") (pintype "passive"))
      (node (ref "IC3") (pin "4") (pinfunction "GNDSIG_4") (pintype "input"))
      (node (ref "IC3") (pin "5") (pinfunction "~{ON/OFF}_5") (pintype "input"))
      (node (ref "IC3") (pin "6") (pinfunction "GND_6") (pintype "power_in"))
      (node (ref "IC7") (pin "11") (pinfunction "T1IN_11") (pintype "input"))
      (node (ref "IC7") (pin "15") (pinfunction "GND_15") (pintype "power_in"))
      (node (ref "IC7") (pin "8") (pinfunction "R2IN_8") (pintype "input"))
      (node (ref "ISP") (pin "6") (pinfunction "6_6") (pintype "passive"))
      (node (ref "JP2") (pin "3") (pinfunction "3_3") (pintype "passive"))
      (node (ref "JP3") (pin "3") (pinfunction "3_3") (pintype "passive"))
      (node (ref "JP4") (pin "3") (pinfunction "3_3") (pintype "passive"))
      (node (ref "JP5") (pin "3") (pinfunction "3_3") (pintype "passive"))
      (node (ref "KICK") (pin "C") (pinfunction "C_C") (pintype "passive"))
      (node (ref "KICK-") (pin "P$1") (pinfunction "P_P$1") (pintype "passive"))
      (node (ref "MOT1-") (pin "P$1") (pinfunction "P_P$1") (pintype "passive"))
      (node (ref "MOT2-") (pin "P$1") (pinfunction "P_P$1") (pintype "passive"))
      (node (ref "R13") (pin "1") (pinfunction "1_1") (pintype "passive"))
      (node (ref "R14") (pin "1") (pinfunction "1_1") (pintype "passive"))
      (node (ref "R19") (pin "1") (pinfunction "1_1") (pintype "passive"))
      (node (ref "R2") (pin "1") (pinfunction "1_1") (pintype "passive"))
      (node (ref "R20") (pin "1") (pinfunction "1_1") (pintype "passive"))
      (node (ref "R21") (pin "1") (pinfunction "1_1") (pintype "passive"))
      (node (ref "R30") (pin "1") (pinfunction "1_1") (pintype "passive"))
      (node (ref "R31") (pin "1") (pinfunction "1_1") (pintype "passive"))
      (node (ref "R42") (pin "1") (pinfunction "1_1") (pintype "passive"))
      (node (ref "R43") (pin "1") (pinfunction "1_1") (pintype "passive"))
      (node (ref "R44") (pin "1") (pinfunction "1_1") (pintype "passive"))
      (node (ref "R46") (pin "1") (pinfunction "1_1") (pintype "passive"))
      (node (ref "R8") (pin "1") (pinfunction "1_1") (pintype "passive"))
      (node (ref "R9") (pin "1") (pinfunction "1_1") (pintype "passive"))
      (node (ref "RJ_1") (pin "P$4") (pinfunction "P$4_P$4") (pintype "bidirectional"))
      (node (ref "RJ_2") (pin "P$4") (pinfunction "P$4_P$4") (pintype "bidirectional"))
      (node (ref "ROT") (pin "C") (pinfunction "C_C") (pintype "passive"))
      (node (ref "RS232") (pin "5") (pinfunction "5_5") (pintype "passive"))
      (node (ref "SV2") (pin "1") (pinfunction "1_1") (pintype "passive"))
      (node (ref "SV2") (pin "2") (pinfunction "2_2") (pintype "passive"))
      (node (ref "SV4") (pin "1") (pinfunction "1_1") (pintype "passive"))
      (node (ref "SV4") (pin "2") (pinfunction "2_2") (pintype "passive"))
      (node (ref "T1") (pin "2") (pinfunction "E_2") (pintype "passive"))
      (node (ref "U$1") (pin "2") (pinfunction "VSS_2") (pintype "passive"))
      (node (ref "U$2") (pin "20") (pinfunction "AGND_20") (pintype "power_in"))
      (node (ref "U$2") (pin "5") (pinfunction "GND_5") (pintype "power_in"))
      (node (ref "VR10") (pin "3") (pinfunction "A_3") (pintype "passive"))
    )
    (net (code "21") (name "ICLED_AKT") (class "Default")
      (node (ref "R25") (pin "1") (pinfunction "1_1") (pintype "passive"))
      (node (ref "R4") (pin "1") (pinfunction "1_1") (pintype "passive"))
      (node (ref "T6") (pin "2") (pinfunction "E_2") (pintype "passive"))
      (node (ref "U$2") (pin "30") (pinfunction "PC0_30") (pintype "bidirectional"))
    )
    (net (code "22") (name "ICLED_GRUEN") (class "Default")
      (node (ref "R12") (pin "1") (pinfunction "1_1") (pintype "passive"))
      (node (ref "R27") (pin "1") (pinfunction "1_1") (pintype "passive"))
      (node (ref "T7") (pin "2") (pinfunction "E_2") (pintype "passive"))
      (node (ref "U$2") (pin "28") (pinfunction "(SCK)PB7_28") (pintype "bidirectional"))
    )
    (net (code "23") (name "ICLED_KICK") (class "Default")
      (node (ref "R24") (pin "1") (pinfunction "1_1") (pintype "passive"))
      (node (ref "R29") (pin "1") (pinfunction "1_1") (pintype "passive"))
      (node (ref "T2") (pin "2") (pinfunction "E_2") (pintype "passive"))
      (node (ref "U$2") (pin "24") (pinfunction "PB4_24") (pintype "bidirectional"))
    )
    (net (code "24") (name "ICLED_ROT") (class "Default")
      (node (ref "R26") (pin "1") (pinfunction "1_1") (pintype "passive"))
      (node (ref "R7") (pin "1") (pinfunction "1_1") (pintype "passive"))
      (node (ref "T5") (pin "2") (pinfunction "E_2") (pintype "passive"))
      (node (ref "U$2") (pin "23") (pinfunction "PB3_23") (pintype "bidirectional"))
    )
    (net (code "25") (name "KICKER") (class "Default")
      (node (ref "IC12") (pin "OUT1") (pinfunction "OUT_OUT1") (pintype "passive"))
      (node (ref "IC12") (pin "OUT2") (pinfunction "OUT_OUT2") (pintype "passive"))
      (node (ref "KICK+") (pin "P$1") (pinfunction "P_P$1") (pintype "passive"))
      (node (ref "R23") (pin "1") (pinfunction "1_1") (pintype "passive"))
    )
    (net (code "26") (name "LED_1") (class "Default")
      (node (ref "SV4") (pin "5") (pinfunction "5_5") (pintype "passive"))
    )
    (net (code "27") (name "LED_2") (class "Default")
      (node (ref "SV4") (pin "3") (pinfunction "3_3") (pintype "passive"))
    )
    (net (code "28") (name "LED_GELB") (class "Default")
      (node (ref "R4") (pin "2") (pinfunction "2_2") (pintype "passive"))
      (node (ref "SV2") (pin "5") (pinfunction "5_5") (pintype "passive"))
    )
    (net (code "29") (name "LED_GRUEN") (class "Default")
      (node (ref "R12") (pin "2") (pinfunction "2_2") (pintype "passive"))
      (node (ref "SV2") (pin "7") (pinfunction "7_7") (pintype "passive"))
    )
    (net (code "30") (name "LED_KICK") (class "Default")
      (node (ref "R24") (pin "2") (pinfunction "2_2") (pintype "passive"))
      (node (ref "SV4") (pin "7") (pinfunction "7_7") (pintype "passive"))
    )
    (net (code "31") (name "LED_ROT") (class "Default")
      (node (ref "R7") (pin "2") (pinfunction "2_2") (pintype "passive"))
      (node (ref "SV2") (pin "3") (pinfunction "3_3") (pintype "passive"))
    )
    (net (code "32") (name "MISO") (class "Default")
      (node (ref "ISP") (pin "1") (pinfunction "1_1") (pintype "passive"))
      (node (ref "U$2") (pin "1") (pinfunction "(MISO_A)PD2_1") (pintype "bidirectional"))
    )
    (net (code "33") (name "MOSI") (class "Default")
      (node (ref "ISP") (pin "4") (pinfunction "4_4") (pintype "passive"))
      (node (ref "JP7") (pin "1") (pinfunction "1_1") (pintype "passive"))
    )
    (net (code "34") (name "MOTION") (class "Default")
      (node (ref "IC4") (pin "1") (pinfunction "OUT1_1") (pintype "passive"))
      (node (ref "IC4") (pin "5") (pinfunction "OUT2_5") (pintype "passive"))
      (node (ref "MOT1+") (pin "P$1") (pinfunction "P_P$1") (pintype "passive"))
      (node (ref "MOT2+") (pin "P$1") (pinfunction "P_P$1") (pintype "passive"))
      (node (ref "R15") (pin "1") (pinfunction "1_1") (pintype "passive"))
    )
    (net (code "35") (name "Net-(5V-PadA)") (class "Default")
      (node (ref "5V") (pin "A") (pinfunction "A_A") (pintype "passive"))
      (node (ref "R18") (pin "1") (pinfunction "1_1") (pintype "passive"))
    )
    (net (code "36") (name "Net-(12V-PadA)") (class "Default")
      (node (ref "12V") (pin "A") (pinfunction "A_A") (pintype "passive"))
      (node (ref "R28") (pin "2") (pinfunction "2_2") (pintype "passive"))
    )
    (net (code "37") (name "Net-(GELB-PadA)") (class "Default")
      (node (ref "GELB") (pin "A") (pinfunction "A_A") (pintype "passive"))
      (node (ref "R25") (pin "2") (pinfunction "2_2") (pintype "passive"))
    )
    (net (code "38") (name "Net-(GRÜN-PadA)") (class "Default")
      (node (ref "GRÜN") (pin "A") (pinfunction "A_A") (pintype "passive"))
      (node (ref "R27") (pin "2") (pinfunction "2_2") (pintype "passive"))
    )
    (net (code "39") (name "Net-(IC3-IN)") (class "Default")
      (node (ref "C3") (pin "+") (pinfunction "+_+") (pintype "passive"))
      (node (ref "F2-0.5A") (pin "2") (pinfunction "2_2") (pintype "passive"))
      (node (ref "IC3") (pin "10") (pinfunction "IN_10") (pintype "input"))
    )
    (net (code "40") (name "Net-(IC3-OUT)") (class "Default")
      (node (ref "D3") (pin "C") (pinfunction "C_C") (pintype "passive"))
      (node (ref "IC3") (pin "12") (pinfunction "OUT_12") (pintype "passive"))
      (node (ref "L3") (pin "1") (pinfunction "1_1") (pintype "passive"))
    )
    (net (code "41") (name "Net-(IC4-IN)") (class "Default")
      (node (ref "IC4") (pin "2") (pinfunction "IN_2") (pintype "input"))
      (node (ref "R48") (pin "2") (pinfunction "2_2") (pintype "passive"))
    )
    (net (code "42") (name "Net-(IC7A-C1+)") (class "Default")
      (node (ref "C18") (pin "2") (pinfunction "2_2") (pintype "passive"))
      (node (ref "IC7") (pin "1") (pinfunction "C1+_1") (pintype "bidirectional"))
    )
    (net (code "43") (name "Net-(IC7A-C1-)") (class "Default")
      (node (ref "C18") (pin "1") (pinfunction "1_1") (pintype "passive"))
      (node (ref "IC7") (pin "3") (pinfunction "C1-_3") (pintype "bidirectional"))
    )
    (net (code "44") (name "Net-(IC7A-C2+)") (class "Default")
      (node (ref "C19") (pin "2") (pinfunction "2_2") (pintype "passive"))
      (node (ref "IC7") (pin "4") (pinfunction "C2+_4") (pintype "bidirectional"))
    )
    (net (code "45") (name "Net-(IC7A-C2-)") (class "Default")
      (node (ref "C19") (pin "1") (pinfunction "1_1") (pintype "passive"))
      (node (ref "IC7") (pin "5") (pinfunction "C2-_5") (pintype "bidirectional"))
    )
    (net (code "46") (name "Net-(IC7A-R1IN)") (class "Default")
      (node (ref "IC7") (pin "13") (pinfunction "R1IN_13") (pintype "input"))
      (node (ref "RS232") (pin "3") (pinfunction "3_3") (pintype "passive"))
    )
    (net (code "47") (name "Net-(IC7A-T2OUT)") (class "Default")
      (node (ref "IC7") (pin "7") (pinfunction "T2OUT_7") (pintype "output"))
      (node (ref "RS232") (pin "1") (pinfunction "1_1") (pintype "passive"))
    )
    (net (code "48") (name "Net-(IC7A-V+)") (class "Default")
      (node (ref "C20") (pin "1") (pinfunction "1_1") (pintype "passive"))
      (node (ref "IC7") (pin "2") (pinfunction "V+_2") (pintype "bidirectional"))
    )
    (net (code "49") (name "Net-(IC7A-V-)") (class "Default")
      (node (ref "C21") (pin "1") (pinfunction "1_1") (pintype "passive"))
      (node (ref "IC7") (pin "6") (pinfunction "V-_6") (pintype "bidirectional"))
    )
    (net (code "50") (name "Net-(IC10-PadIN)") (class "Default")
      (node (ref "IC10") (pin "IN") (pinfunction "IN_IN") (pintype "input"))
      (node (ref "R50") (pin "2") (pinfunction "2_2") (pintype "passive"))
    )
    (net (code "51") (name "Net-(IC11-PadIN)") (class "Default")
      (node (ref "IC11") (pin "IN") (pinfunction "IN_IN") (pintype "input"))
      (node (ref "R49") (pin "2") (pinfunction "2_2") (pintype "passive"))
    )
    (net (code "52") (name "Net-(IC12-PadIN)") (class "Default")
      (node (ref "IC12") (pin "IN") (pinfunction "IN_IN") (pintype "input"))
      (node (ref "R47") (pin "2") (pinfunction "2_2") (pintype "passive"))
    )
    (net (code "53") (name "Net-(IC15-PadIN)") (class "Default")
      (node (ref "IC15") (pin "IN") (pinfunction "IN_IN") (pintype "input"))
      (node (ref "R22") (pin "2") (pinfunction "2_2") (pintype "passive"))
    )
    (net (code "54") (name "Net-(JP1-Pad1)") (class "Default")
      (node (ref "JP1") (pin "1") (pinfunction "1_1") (pintype "passive"))
      (node (ref "R6") (pin "2") (pinfunction "2_2") (pintype "passive"))
    )
    (net (code "55") (name "Net-(KICK-PadA)") (class "Default")
      (node (ref "KICK") (pin "A") (pinfunction "A_A") (pintype "passive"))
      (node (ref "R29") (pin "2") (pinfunction "2_2") (pintype "passive"))
    )
    (net (code "56") (name "Net-(R26-Pad2)") (class "Default")
      (node (ref "R26") (pin "2") (pinfunction "2_2") (pintype "passive"))
      (node (ref "ROT") (pin "A") (pinfunction "A_A") (pintype "passive"))
    )
    (net (code "57") (name "Net-(R36-Pad1)") (class "Default")
      (node (ref "R36") (pin "1") (pinfunction "1_1") (pintype "passive"))
      (node (ref "R44") (pin "2") (pinfunction "2_2") (pintype "passive"))
    )
    (net (code "58") (name "Net-(R38-Pad1)") (class "Default")
      (node (ref "R38") (pin "1") (pinfunction "1_1") (pintype "passive"))
      (node (ref "R42") (pin "2") (pinfunction "2_2") (pintype "passive"))
    )
    (net (code "59") (name "Net-(R40-Pad1)") (class "Default")
      (node (ref "R40") (pin "1") (pinfunction "1_1") (pintype "passive"))
      (node (ref "R43") (pin "2") (pinfunction "2_2") (pintype "passive"))
    )
    (net (code "60") (name "Net-(RJ_1-PadP$1)") (class "Default")
      (node (ref "RJ_1") (pin "P$1") (pinfunction "P$1_P$1") (pintype "bidirectional"))
      (node (ref "RJ_2") (pin "P$1") (pinfunction "P$1_P$1") (pintype "bidirectional"))
      (node (ref "SJ2") (pin "2") (pinfunction "2_2") (pintype "passive"))
    )
    (net (code "61") (name "Net-(T1-B)") (class "Default")
      (node (ref "R5") (pin "2") (pinfunction "2_2") (pintype "passive"))
      (node (ref "T1") (pin "1") (pinfunction "B_1") (pintype "passive"))
    )
    (net (code "62") (name "Net-(T1-C)") (class "Default")
      (node (ref "T1") (pin "3") (pinfunction "C_3") (pintype "passive"))
      (node (ref "TDB-05") (pin "-") (pinfunction "2_-") (pintype "passive"))
    )
    (net (code "63") (name "Net-(T2-B)") (class "Default")
      (node (ref "R23") (pin "2") (pinfunction "2_2") (pintype "passive"))
      (node (ref "T2") (pin "1") (pinfunction "B_1") (pintype "passive"))
    )
    (net (code "64") (name "Net-(T5-B)") (class "Default")
      (node (ref "R16") (pin "2") (pinfunction "2_2") (pintype "passive"))
      (node (ref "T5") (pin "1") (pinfunction "B_1") (pintype "passive"))
    )
    (net (code "65") (name "Net-(T6-B)") (class "Default")
      (node (ref "R17") (pin "2") (pinfunction "2_2") (pintype "passive"))
      (node (ref "T6") (pin "1") (pinfunction "B_1") (pintype "passive"))
    )
    (net (code "66") (name "Net-(T7-B)") (class "Default")
      (node (ref "R15") (pin "2") (pinfunction "2_2") (pintype "passive"))
      (node (ref "T7") (pin "1") (pinfunction "B_1") (pintype "passive"))
    )
    (net (code "67") (name "Net-(U$1-RS)") (class "Default")
      (node (ref "R31") (pin "2") (pinfunction "2_2") (pintype "passive"))
      (node (ref "U$1") (pin "8") (pinfunction "RS_8") (pintype "input"))
    )
    (net (code "68") (name "Net-(U$2-(MOSI_A{slash}TXD)PD3)") (class "Default")
      (node (ref "JP7") (pin "2") (pinfunction "2_2") (pintype "passive"))
      (node (ref "U$2") (pin "2") (pinfunction "(MOSI_A/TXD)PD3_2") (pintype "bidirectional"))
    )
    (net (code "69") (name "Net-(U$2-(RXD)PD4)") (class "Default")
      (node (ref "JP6") (pin "2") (pinfunction "2_2") (pintype "passive"))
      (node (ref "U$2") (pin "12") (pinfunction "(RXD)PD4_12") (pintype "bidirectional"))
    )
    (net (code "70") (name "Net-(U$2-AREF)") (class "Default")
      (node (ref "C14") (pin "2") (pinfunction "2_2") (pintype "passive"))
      (node (ref "U$2") (pin "21") (pinfunction "AREF_21") (pintype "bidirectional"))
    )
    (net (code "71") (name "Net-(U$2-AVCC)") (class "Default")
      (node (ref "C16") (pin "1") (pinfunction "1_1") (pintype "passive"))
      (node (ref "L1") (pin "1") (pinfunction "1_1") (pintype "passive"))
      (node (ref "U$2") (pin "19") (pinfunction "AVCC_19") (pintype "bidirectional"))
    )
    (net (code "72") (name "Net-(U$2-PE1(XTAL1))") (class "Default")
      (node (ref "C11") (pin "2") (pinfunction "2_2") (pintype "passive"))
      (node (ref "Q1") (pin "1") (pinfunction "1_1") (pintype "passive"))
      (node (ref "U$2") (pin "10") (pinfunction "PE1(XTAL1)_10") (pintype "bidirectional"))
    )
    (net (code "73") (name "Net-(U$2-PE2(XTAL2))") (class "Default")
      (node (ref "C10") (pin "2") (pinfunction "2_2") (pintype "passive"))
      (node (ref "Q1") (pin "2") (pinfunction "2_2") (pintype "passive"))
      (node (ref "U$2") (pin "11") (pinfunction "PE2(XTAL2)_11") (pintype "bidirectional"))
    )
    (net (code "74") (name "Net-(VR6-A)") (class "Default")
      (node (ref "JP5") (pin "2") (pinfunction "2_2") (pintype "passive"))
      (node (ref "R22") (pin "1") (pinfunction "1_1") (pintype "passive"))
      (node (ref "VR6") (pin "3") (pinfunction "A_3") (pintype "passive"))
    )
    (net (code "75") (name "Net-(VR6-C)") (class "Default")
      (node (ref "R50") (pin "1") (pinfunction "1_1") (pintype "passive"))
      (node (ref "VR6") (pin "1") (pinfunction "C_1") (pintype "passive"))
    )
    (net (code "76") (name "Net-(VR7-A)") (class "Default")
      (node (ref "JP2") (pin "2") (pinfunction "2_2") (pintype "passive"))
      (node (ref "VR7") (pin "3") (pinfunction "A_3") (pintype "passive"))
    )
    (net (code "77") (name "Net-(VR7-C)") (class "Default")
      (node (ref "R49") (pin "1") (pinfunction "1_1") (pintype "passive"))
      (node (ref "VR7") (pin "1") (pinfunction "C_1") (pintype "passive"))
    )
    (net (code "78") (name "Net-(VR7-R)") (class "Default")
      (node (ref "R36") (pin "2") (pinfunction "2_2") (pintype "passive"))
      (node (ref "R37") (pin "1") (pinfunction "1_1") (pintype "passive"))
      (node (ref "VR7") (pin "2") (pinfunction "R_2") (pintype "passive"))
    )
    (net (code "79") (name "Net-(VR8-A)") (class "Default")
      (node (ref "JP3") (pin "2") (pinfunction "2_2") (pintype "passive"))
      (node (ref "VR8") (pin "3") (pinfunction "A_3") (pintype "passive"))
    )
    (net (code "80") (name "Net-(VR8-C)") (class "Default")
      (node (ref "R47") (pin "1") (pinfunction "1_1") (pintype "passive"))
      (node (ref "VR8") (pin "1") (pinfunction "C_1") (pintype "passive"))
    )
    (net (code "81") (name "Net-(VR8-R)") (class "Default")
      (node (ref "R38") (pin "2") (pinfunction "2_2") (pintype "passive"))
      (node (ref "R39") (pin "1") (pinfunction "1_1") (pintype "passive"))
      (node (ref "VR8") (pin "2") (pinfunction "R_2") (pintype "passive"))
    )
    (net (code "82") (name "Net-(VR9-A)") (class "Default")
      (node (ref "JP4") (pin "2") (pinfunction "2_2") (pintype "passive"))
      (node (ref "VR9") (pin "3") (pinfunction "A_3") (pintype "passive"))
    )
    (net (code "83") (name "Net-(VR9-C)") (class "Default")
      (node (ref "R48") (pin "1") (pinfunction "1_1") (pintype "passive"))
      (node (ref "VR9") (pin "1") (pinfunction "C_1") (pintype "passive"))
    )
    (net (code "84") (name "Net-(VR9-R)") (class "Default")
      (node (ref "R40") (pin "2") (pinfunction "2_2") (pintype "passive"))
      (node (ref "R41") (pin "1") (pinfunction "1_1") (pintype "passive"))
      (node (ref "VR9") (pin "2") (pinfunction "R_2") (pintype "passive"))
    )
    (net (code "85") (name "Net-(VR10-C)") (class "Default")
      (node (ref "R30") (pin "2") (pinfunction "2_2") (pintype "passive"))
      (node (ref "R35") (pin "1") (pinfunction "1_1") (pintype "passive"))
      (node (ref "VR10") (pin "1") (pinfunction "C_1") (pintype "passive"))
      (node (ref "VR6") (pin "2") (pinfunction "R_2") (pintype "passive"))
    )
    (net (code "86") (name "Net-(VR10-R)") (class "Default")
      (node (ref "R45") (pin "1") (pinfunction "1_1") (pintype "passive"))
      (node (ref "R46") (pin "2") (pinfunction "2_2") (pintype "passive"))
      (node (ref "VR10") (pin "2") (pinfunction "R_2") (pintype "passive"))
    )
    (net (code "87") (name "RESET") (class "Default")
      (node (ref "ISP") (pin "5") (pinfunction "5_5") (pintype "passive"))
    )
    (net (code "88") (name "RST") (class "Default")
      (node (ref "C13") (pin "2") (pinfunction "2_2") (pintype "passive"))
      (node (ref "R1") (pin "1") (pinfunction "1_1") (pintype "passive"))
      (node (ref "U$2") (pin "31") (pinfunction "PE0(RESET)_31") (pintype "input"))
    )
    (net (code "89") (name "RXCAN") (class "Default")
      (node (ref "U$1") (pin "4") (pinfunction "RXD_4") (pintype "output"))
      (node (ref "U$2") (pin "7") (pinfunction "(RXCAN)PC3_7") (pintype "bidirectional"))
    )
    (net (code "90") (name "RXD") (class "Default")
      (node (ref "IC7") (pin "12") (pinfunction "R1OUT_12") (pintype "output"))
      (node (ref "JP6") (pin "3") (pinfunction "3_3") (pintype "passive"))
    )
    (net (code "91") (name "SCK") (class "Default")
      (node (ref "ISP") (pin "3") (pinfunction "3_3") (pintype "passive"))
      (node (ref "JP6") (pin "1") (pinfunction "1_1") (pintype "passive"))
    )
    (net (code "92") (name "SPEAKER") (class "Default")
      (node (ref "R5") (pin "1") (pinfunction "1_1") (pintype "passive"))
      (node (ref "U$2") (pin "29") (pinfunction "PD0_29") (pintype "bidirectional"))
    )
    (net (code "93") (name "SW_1") (class "Default")
      (node (ref "SV4") (pin "6") (pinfunction "6_6") (pintype "passive"))
      (node (ref "U$2") (pin "3") (pinfunction "PC1_3") (pintype "bidirectional"))
    )
    (net (code "94") (name "SW_2") (class "Default")
      (node (ref "SV4") (pin "4") (pinfunction "4_4") (pintype "passive"))
    )
    (net (code "95") (name "SW_12V") (class "Default")
      (node (ref "JP5") (pin "1") (pinfunction "1_1") (pintype "passive"))
      (node (ref "SV2") (pin "4") (pinfunction "4_4") (pintype "passive"))
      (node (ref "U$2") (pin "15") (pinfunction "PD7_15") (pintype "bidirectional"))
    )
    (net (code "96") (name "SW_AKT") (class "Default")
      (node (ref "JP2") (pin "1") (pinfunction "1_1") (pintype "passive"))
      (node (ref "JP9") (pin "2") (pinfunction "2_2") (pintype "passive"))
      (node (ref "SV2") (pin "6") (pinfunction "6_6") (pintype "passive"))
      (node (ref "U$2") (pin "8") (pinfunction "PB0_8") (pintype "bidirectional"))
    )
    (net (code "97") (name "SW_KICK") (class "Default")
      (node (ref "JP3") (pin "1") (pinfunction "1_1") (pintype "passive"))
      (node (ref "JP9") (pin "1") (pinfunction "1_1") (pintype "passive"))
      (node (ref "SV4") (pin "8") (pinfunction "8_8") (pintype "passive"))
      (node (ref "U$2") (pin "25") (pinfunction "PC7_25") (pintype "bidirectional"))
    )
    (net (code "98") (name "SW_MOT") (class "Default")
      (node (ref "JP4") (pin "1") (pinfunction "1_1") (pintype "passive"))
      (node (ref "SV2") (pin "8") (pinfunction "8_8") (pintype "passive"))
      (node (ref "U$2") (pin "9") (pinfunction "PB1_9") (pintype "bidirectional"))
    )
    (net (code "99") (name "TXCAN") (class "Default")
      (node (ref "U$1") (pin "1") (pinfunction "TXD_1") (pintype "input"))
      (node (ref "U$2") (pin "6") (pinfunction "(TXCAN)PC2_6") (pintype "bidirectional"))
    )
    (net (code "100") (name "TXD") (class "Default")
      (node (ref "IC7") (pin "10") (pinfunction "T2IN_10") (pintype "input"))
      (node (ref "JP7") (pin "3") (pinfunction "3_3") (pintype "passive"))
    )
    (net (code "101") (name "unconnected-(IC7A-R2OUT-Pad9)") (class "Default")
      (node (ref "IC7") (pin "9") (pinfunction "R2OUT_9") (pintype "output"))
    )
    (net (code "102") (name "unconnected-(IC7A-T1OUT-Pad14)") (class "Default")
      (node (ref "IC7") (pin "14") (pinfunction "T1OUT_14") (pintype "output"))
    )
    (net (code "103") (name "unconnected-(RS232-Pad2)") (class "Default")
      (node (ref "RS232") (pin "2") (pinfunction "2_2") (pintype "passive"))
    )
    (net (code "104") (name "unconnected-(RS232-Pad4)") (class "Default")
      (node (ref "RS232") (pin "4") (pinfunction "4_4") (pintype "passive"))
    )
    (net (code "105") (name "unconnected-(RS232-Pad6)") (class "Default")
      (node (ref "RS232") (pin "6") (pinfunction "6_6") (pintype "passive"))
    )
    (net (code "106") (name "unconnected-(U$1-VREF-Pad5)") (class "Default")
      (node (ref "U$1") (pin "5") (pinfunction "VREF_5") (pintype "output"))
    )
  )
)
